# tm.net
KiCad netlist of a schematic drawn in Altium Designer
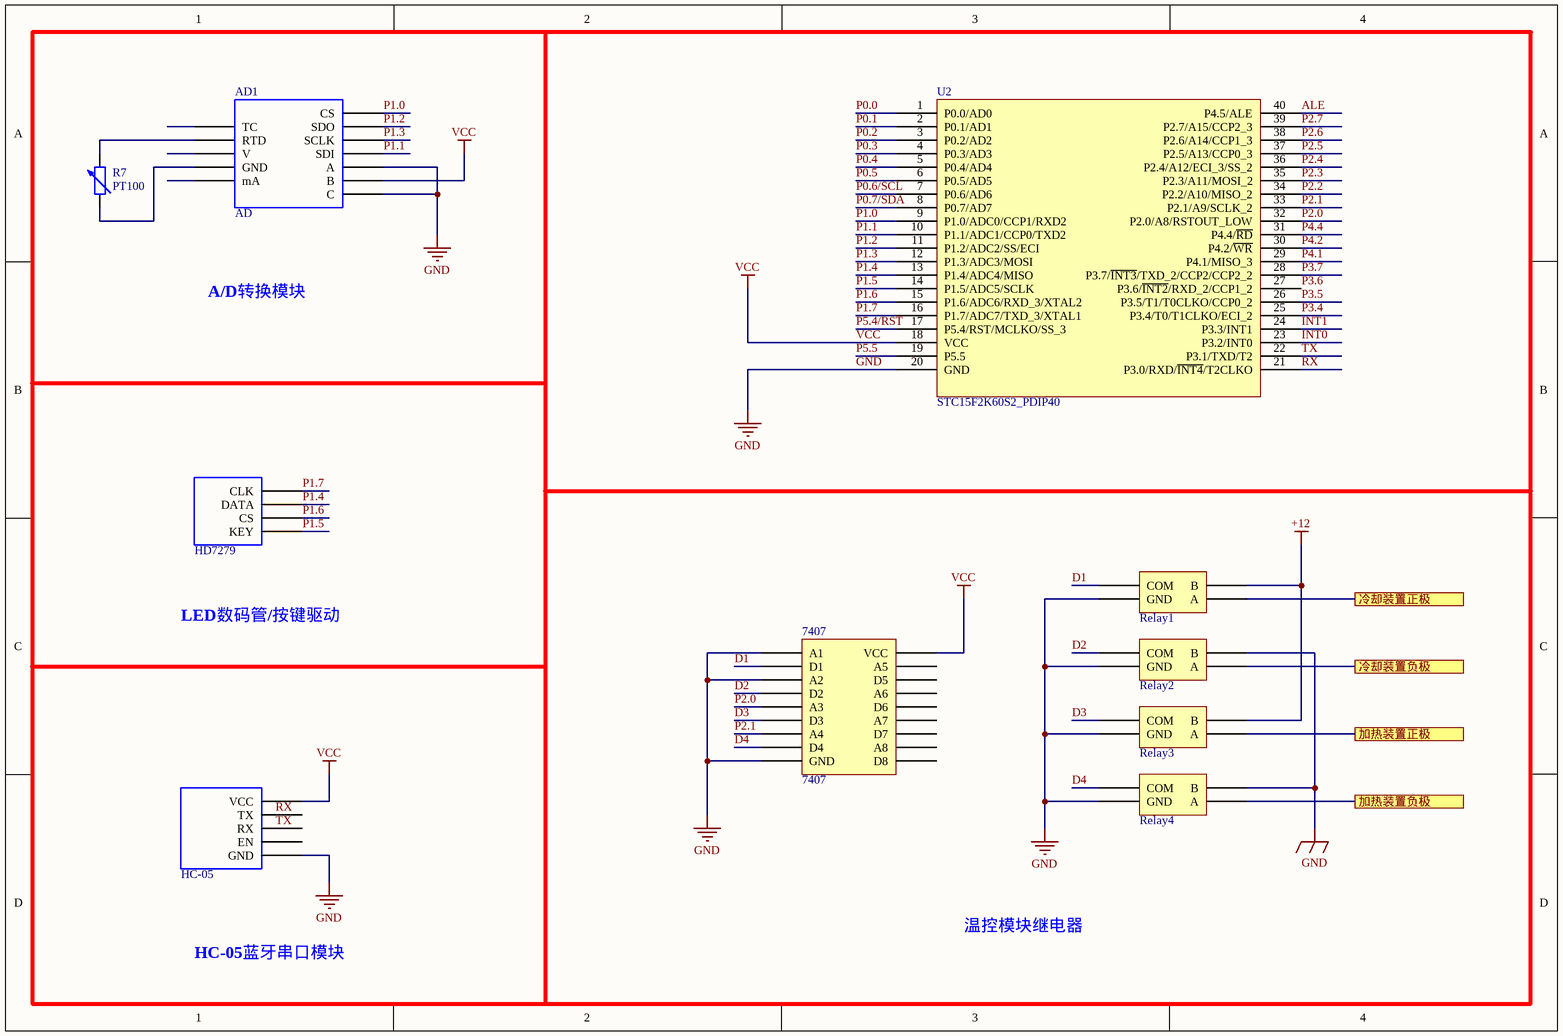
[diagram p0: tm.SchDoc]

(export (version "E")
  (design (tool "Eeschema 10.0.6"))
  (components
    (comp (ref "*1") (value "HD7279") (libsource (lib "expbox") (part "HD7279_")))
    (comp (ref "2") (value "HC-05") (libsource (lib "hc05") (part "HC-05")))
    (comp (ref "7407") (value "7407") (libsource (lib "expbox") (part "7407")))
    (comp (ref "AD1") (value "AD") (libsource (lib "expbox") (part "AD_Module")))
    (comp (ref "R7")
      (value "PT100")
      (footprint "AXIAL-0.6")
      (description "Variable Resistor")
      (fields (field (name "PUBLISHER") "Altium Limited"))
      (libsource (lib "Miscellaneous Devices") (part "Res Adj2"))
    )
    (comp (ref "Relay1") (value "Relay") (libsource (lib "expbox") (part "relay")))
    (comp (ref "Relay2") (value "Relay") (libsource (lib "expbox") (part "relay")))
    (comp (ref "Relay3") (value "Relay") (libsource (lib "expbox") (part "relay")))
    (comp (ref "Relay4") (value "Relay") (libsource (lib "expbox") (part "relay")))
    (comp (ref "U2")
      (value "STC15F2K60S2_PDIP40")
      (footprint "DIP40")
      (libsource (lib "stcmcu_altium_lib") (part "STC15F2K60S2_PDIP40"))
    )
  )
  (nets
    (net (code "1") (name "+12") (class "Default")
      (node (ref "Relay1") (pin "87") (pinfunction "B_87") (pintype "passive"))
      (node (ref "Relay3") (pin "87") (pinfunction "B_87") (pintype "passive"))
    )
    (net (code "2") (name "/ALE") (class "Default")
      (node (ref "U2") (pin "40") (pinfunction "P4.5/ALE_40") (pintype "passive"))
    )
    (net (code "3") (name "/D1") (class "Default")
      (node (ref "7407") (pin "63") (pinfunction "D1_63") (pintype "passive"))
      (node (ref "Relay1") (pin "84") (pinfunction "COM_84") (pintype "passive"))
    )
    (net (code "4") (name "/D2") (class "Default")
      (node (ref "7407") (pin "65") (pinfunction "D2_65") (pintype "passive"))
      (node (ref "Relay2") (pin "84") (pinfunction "COM_84") (pintype "passive"))
    )
    (net (code "5") (name "/D3") (class "Default")
      (node (ref "7407") (pin "67") (pinfunction "D3_67") (pintype "passive"))
      (node (ref "Relay3") (pin "84") (pinfunction "COM_84") (pintype "passive"))
    )
    (net (code "6") (name "/D4") (class "Default")
      (node (ref "7407") (pin "69") (pinfunction "D4_69") (pintype "passive"))
      (node (ref "Relay4") (pin "84") (pinfunction "COM_84") (pintype "passive"))
    )
    (net (code "7") (name "/INT0") (class "Default")
      (node (ref "U2") (pin "23") (pinfunction "P3.2/INT0_23") (pintype "passive"))
    )
    (net (code "8") (name "/INT1") (class "Default")
      (node (ref "U2") (pin "24") (pinfunction "P3.3/INT1_24") (pintype "passive"))
    )
    (net (code "9") (name "/P0.0") (class "Default")
      (node (ref "U2") (pin "1") (pinfunction "P0.0/AD0_1") (pintype "passive"))
    )
    (net (code "10") (name "/P0.1") (class "Default")
      (node (ref "U2") (pin "2") (pinfunction "P0.1/AD1_2") (pintype "passive"))
    )
    (net (code "11") (name "/P0.2") (class "Default")
      (node (ref "U2") (pin "3") (pinfunction "P0.2/AD2_3") (pintype "passive"))
    )
    (net (code "12") (name "/P0.3") (class "Default")
      (node (ref "U2") (pin "4") (pinfunction "P0.3/AD3_4") (pintype "passive"))
    )
    (net (code "13") (name "/P0.4") (class "Default")
      (node (ref "U2") (pin "5") (pinfunction "P0.4/AD4_5") (pintype "passive"))
    )
    (net (code "14") (name "/P0.5") (class "Default")
      (node (ref "U2") (pin "6") (pinfunction "P0.5/AD5_6") (pintype "passive"))
    )
    (net (code "15") (name "/P0.6{slash}SCL") (class "Default")
      (node (ref "U2") (pin "7") (pinfunction "P0.6/AD6_7") (pintype "passive"))
    )
    (net (code "16") (name "/P0.7{slash}SDA") (class "Default")
      (node (ref "U2") (pin "8") (pinfunction "P0.7/AD7_8") (pintype "passive"))
    )
    (net (code "17") (name "/P1.0") (class "Default")
      (node (ref "AD1") (pin "44") (pinfunction "CS_44") (pintype "passive"))
      (node (ref "U2") (pin "9") (pinfunction "P1.0/ADC0/CCP1/RXD2_9") (pintype "passive"))
    )
    (net (code "18") (name "/P1.1") (class "Default")
      (node (ref "AD1") (pin "47") (pinfunction "SDI_47") (pintype "passive"))
      (node (ref "U2") (pin "10") (pinfunction "P1.1/ADC1/CCP0/TXD2_10") (pintype "passive"))
    )
    (net (code "19") (name "/P1.2") (class "Default")
      (node (ref "AD1") (pin "45") (pinfunction "SDO_45") (pintype "passive"))
      (node (ref "U2") (pin "11") (pinfunction "P1.2/ADC2/SS/ECI_11") (pintype "passive"))
    )
    (net (code "20") (name "/P1.3") (class "Default")
      (node (ref "AD1") (pin "46") (pinfunction "SCLK_46") (pintype "passive"))
      (node (ref "U2") (pin "12") (pinfunction "P1.3/ADC3/MOSI_12") (pintype "passive"))
    )
    (net (code "21") (name "/P1.4") (class "Default")
      (node (ref "*1") (pin "30") (pinfunction "DATA_30") (pintype "passive"))
      (node (ref "U2") (pin "13") (pinfunction "P1.4/ADC4/MISO_13") (pintype "passive"))
    )
    (net (code "22") (name "/P1.5") (class "Default")
      (node (ref "*1") (pin "32") (pinfunction "KEY_32") (pintype "passive"))
      (node (ref "U2") (pin "14") (pinfunction "P1.5/ADC5/SCLK_14") (pintype "passive"))
    )
    (net (code "23") (name "/P1.6") (class "Default")
      (node (ref "*1") (pin "31") (pinfunction "CS_31") (pintype "passive"))
      (node (ref "U2") (pin "15") (pinfunction "P1.6/ADC6/RXD_3/XTAL2_15") (pintype "passive"))
    )
    (net (code "24") (name "/P1.7") (class "Default")
      (node (ref "*1") (pin "29") (pinfunction "CLK_29") (pintype "passive"))
      (node (ref "U2") (pin "16") (pinfunction "P1.7/ADC7/TXD_3/XTAL1_16") (pintype "passive"))
    )
    (net (code "25") (name "/P2.0") (class "Default")
      (node (ref "7407") (pin "66") (pinfunction "A3_66") (pintype "passive"))
      (node (ref "U2") (pin "32") (pinfunction "P2.0/A8/RSTOUT_LOW_32") (pintype "passive"))
    )
    (net (code "26") (name "/P2.1") (class "Default")
      (node (ref "7407") (pin "68") (pinfunction "A4_68") (pintype "passive"))
      (node (ref "U2") (pin "33") (pinfunction "P2.1/A9/SCLK_2_33") (pintype "passive"))
    )
    (net (code "27") (name "/P2.2") (class "Default")
      (node (ref "U2") (pin "34") (pinfunction "P2.2/A10/MISO_2_34") (pintype "passive"))
    )
    (net (code "28") (name "/P2.3") (class "Default")
      (node (ref "U2") (pin "35") (pinfunction "P2.3/A11/MOSI_2_35") (pintype "passive"))
    )
    (net (code "29") (name "/P2.4") (class "Default")
      (node (ref "U2") (pin "36") (pinfunction "P2.4/A12/ECI_3/SS_2_36") (pintype "passive"))
    )
    (net (code "30") (name "/P2.5") (class "Default")
      (node (ref "U2") (pin "37") (pinfunction "P2.5/A13/CCP0_3_37") (pintype "passive"))
    )
    (net (code "31") (name "/P2.6") (class "Default")
      (node (ref "U2") (pin "38") (pinfunction "P2.6/A14/CCP1_3_38") (pintype "passive"))
    )
    (net (code "32") (name "/P2.7") (class "Default")
      (node (ref "U2") (pin "39") (pinfunction "P2.7/A15/CCP2_3_39") (pintype "passive"))
    )
    (net (code "33") (name "/P3.4") (class "Default")
      (node (ref "U2") (pin "25") (pinfunction "P3.4/T0/T1CLKO/ECI_2_25") (pintype "passive"))
    )
    (net (code "34") (name "/P3.5") (class "Default")
      (node (ref "U2") (pin "26") (pinfunction "P3.5/T1/T0CLKO/CCP0_2_26") (pintype "passive"))
    )
    (net (code "35") (name "/P3.6") (class "Default")
      (node (ref "U2") (pin "27") (pinfunction "P3.6/~{INT2}/RXD_2/CCP1_2_27") (pintype "passive"))
    )
    (net (code "36") (name "/P3.7") (class "Default")
      (node (ref "U2") (pin "28") (pinfunction "P3.7/~{INT3}/TXD_2/CCP2/CCP2_2_28") (pintype "passive"))
    )
    (net (code "37") (name "/P4.1") (class "Default")
      (node (ref "U2") (pin "29") (pinfunction "P4.1/MISO_3_29") (pintype "passive"))
    )
    (net (code "38") (name "/P4.2") (class "Default")
      (node (ref "U2") (pin "30") (pinfunction "P4.2/~{WR}_30") (pintype "passive"))
    )
    (net (code "39") (name "/P4.4") (class "Default")
      (node (ref "U2") (pin "31") (pinfunction "P4.4/~{RD}_31") (pintype "passive"))
    )
    (net (code "40") (name "/P5.4{slash}RST") (class "Default")
      (node (ref "U2") (pin "17") (pinfunction "P5.4/RST/MCLKO/SS_3_17") (pintype "passive"))
    )
    (net (code "41") (name "/P5.5") (class "Default")
      (node (ref "U2") (pin "19") (pinfunction "P5.5_19") (pintype "passive"))
    )
    (net (code "42") (name "/RX") (class "Default")
      (node (ref "U2") (pin "21") (pinfunction "P3.0/RXD/~{INT4}/T2CLKO_21") (pintype "passive"))
    )
    (net (code "43") (name "/TX") (class "Default")
      (node (ref "U2") (pin "22") (pinfunction "P3.1/TXD/T2_22") (pintype "passive"))
    )
    (net (code "44") (name "/冷却装置正极") (class "Default")
      (node (ref "Relay1") (pin "86") (pinfunction "A_86") (pintype "passive"))
    )
    (net (code "45") (name "/冷却装置负极") (class "Default")
      (node (ref "Relay2") (pin "86") (pinfunction "A_86") (pintype "passive"))
    )
    (net (code "46") (name "/加热装置正极") (class "Default")
      (node (ref "Relay3") (pin "86") (pinfunction "A_86") (pintype "passive"))
    )
    (net (code "47") (name "/加热装置负极") (class "Default")
      (node (ref "Relay4") (pin "86") (pinfunction "A_86") (pintype "passive"))
    )
    (net (code "48") (name "GND") (class "Default")
      (node (ref "2") (pin "37") (pinfunction "GND_37") (pintype "passive"))
      (node (ref "7407") (pin "62") (pinfunction "A1_62") (pintype "passive"))
      (node (ref "7407") (pin "64") (pinfunction "A2_64") (pintype "passive"))
      (node (ref "7407") (pin "70") (pinfunction "GND_70") (pintype "passive"))
      (node (ref "AD1") (pin "48") (pinfunction "A_48") (pintype "passive"))
      (node (ref "AD1") (pin "50") (pinfunction "C_50") (pintype "passive"))
      (node (ref "Relay1") (pin "85") (pinfunction "GND_85") (pintype "passive"))
      (node (ref "Relay2") (pin "85") (pinfunction "GND_85") (pintype "passive"))
      (node (ref "Relay2") (pin "87") (pinfunction "B_87") (pintype "passive"))
      (node (ref "Relay3") (pin "85") (pinfunction "GND_85") (pintype "passive"))
      (node (ref "Relay4") (pin "85") (pinfunction "GND_85") (pintype "passive"))
      (node (ref "Relay4") (pin "87") (pinfunction "B_87") (pintype "passive"))
      (node (ref "U2") (pin "20") (pinfunction "GND_20") (pintype "passive"))
    )
    (net (code "49") (name "Net-(AD1-GND)") (class "Default")
      (node (ref "AD1") (pin "51") (pinfunction "GND_51") (pintype "passive"))
      (node (ref "R7") (pin "1") (pinfunction "1_1") (pintype "passive"))
    )
    (net (code "50") (name "Net-(AD1-RTD)") (class "Default")
      (node (ref "AD1") (pin "53") (pinfunction "RTD_53") (pintype "passive"))
      (node (ref "R7") (pin "2") (pinfunction "2_2") (pintype "passive"))
    )
    (net (code "51") (name "VCC") (class "Default")
      (node (ref "2") (pin "33") (pinfunction "VCC_33") (pintype "passive"))
      (node (ref "7407") (pin "56") (pinfunction "VCC_56") (pintype "passive"))
      (node (ref "AD1") (pin "49") (pinfunction "B_49") (pintype "passive"))
      (node (ref "U2") (pin "18") (pinfunction "VCC_18") (pintype "passive"))
    )
    (net (code "52") (name "unconnected-(2-EN-Pad36)") (class "Default")
      (node (ref "2") (pin "36") (pinfunction "EN_36") (pintype "passive"))
    )
    (net (code "53") (name "unconnected-(2-RX-Pad35)") (class "Default")
      (node (ref "2") (pin "35") (pinfunction "RX_35") (pintype "passive"))
    )
    (net (code "54") (name "unconnected-(2-TX-Pad34)") (class "Default")
      (node (ref "2") (pin "34") (pinfunction "TX_34") (pintype "passive"))
    )
    (net (code "55") (name "unconnected-(7407-A5-Pad57)") (class "Default")
      (node (ref "7407") (pin "57") (pinfunction "A5_57") (pintype "passive"))
    )
    (net (code "56") (name "unconnected-(7407-A6-Pad59)") (class "Default")
      (node (ref "7407") (pin "59") (pinfunction "A6_59") (pintype "passive"))
    )
    (net (code "57") (name "unconnected-(7407-A7-Pad61)") (class "Default")
      (node (ref "7407") (pin "61") (pinfunction "A7_61") (pintype "passive"))
    )
    (net (code "58") (name "unconnected-(7407-A8-Pad72)") (class "Default")
      (node (ref "7407") (pin "72") (pinfunction "A8_72") (pintype "passive"))
    )
    (net (code "59") (name "unconnected-(7407-D5-Pad58)") (class "Default")
      (node (ref "7407") (pin "58") (pinfunction "D5_58") (pintype "passive"))
    )
    (net (code "60") (name "unconnected-(7407-D6-Pad60)") (class "Default")
      (node (ref "7407") (pin "60") (pinfunction "D6_60") (pintype "passive"))
    )
    (net (code "61") (name "unconnected-(7407-D7-Pad71)") (class "Default")
      (node (ref "7407") (pin "71") (pinfunction "D7_71") (pintype "passive"))
    )
    (net (code "62") (name "unconnected-(7407-D8-Pad73)") (class "Default")
      (node (ref "7407") (pin "73") (pinfunction "D8_73") (pintype "passive"))
    )
    (net (code "63") (name "unconnected-(AD1-TC-Pad52)") (class "Default")
      (node (ref "AD1") (pin "52") (pinfunction "TC_52") (pintype "passive"))
    )
    (net (code "64") (name "unconnected-(AD1-V-Pad54)") (class "Default")
      (node (ref "AD1") (pin "54") (pinfunction "V_54") (pintype "passive"))
    )
    (net (code "65") (name "unconnected-(AD1-mA-Pad55)") (class "Default")
      (node (ref "AD1") (pin "55") (pinfunction "mA_55") (pintype "passive"))
    )
  )
)
